# 2021-06-23_AD590_HIH-4031.net
KiCad netlist of a schematic drawn in EAGLE
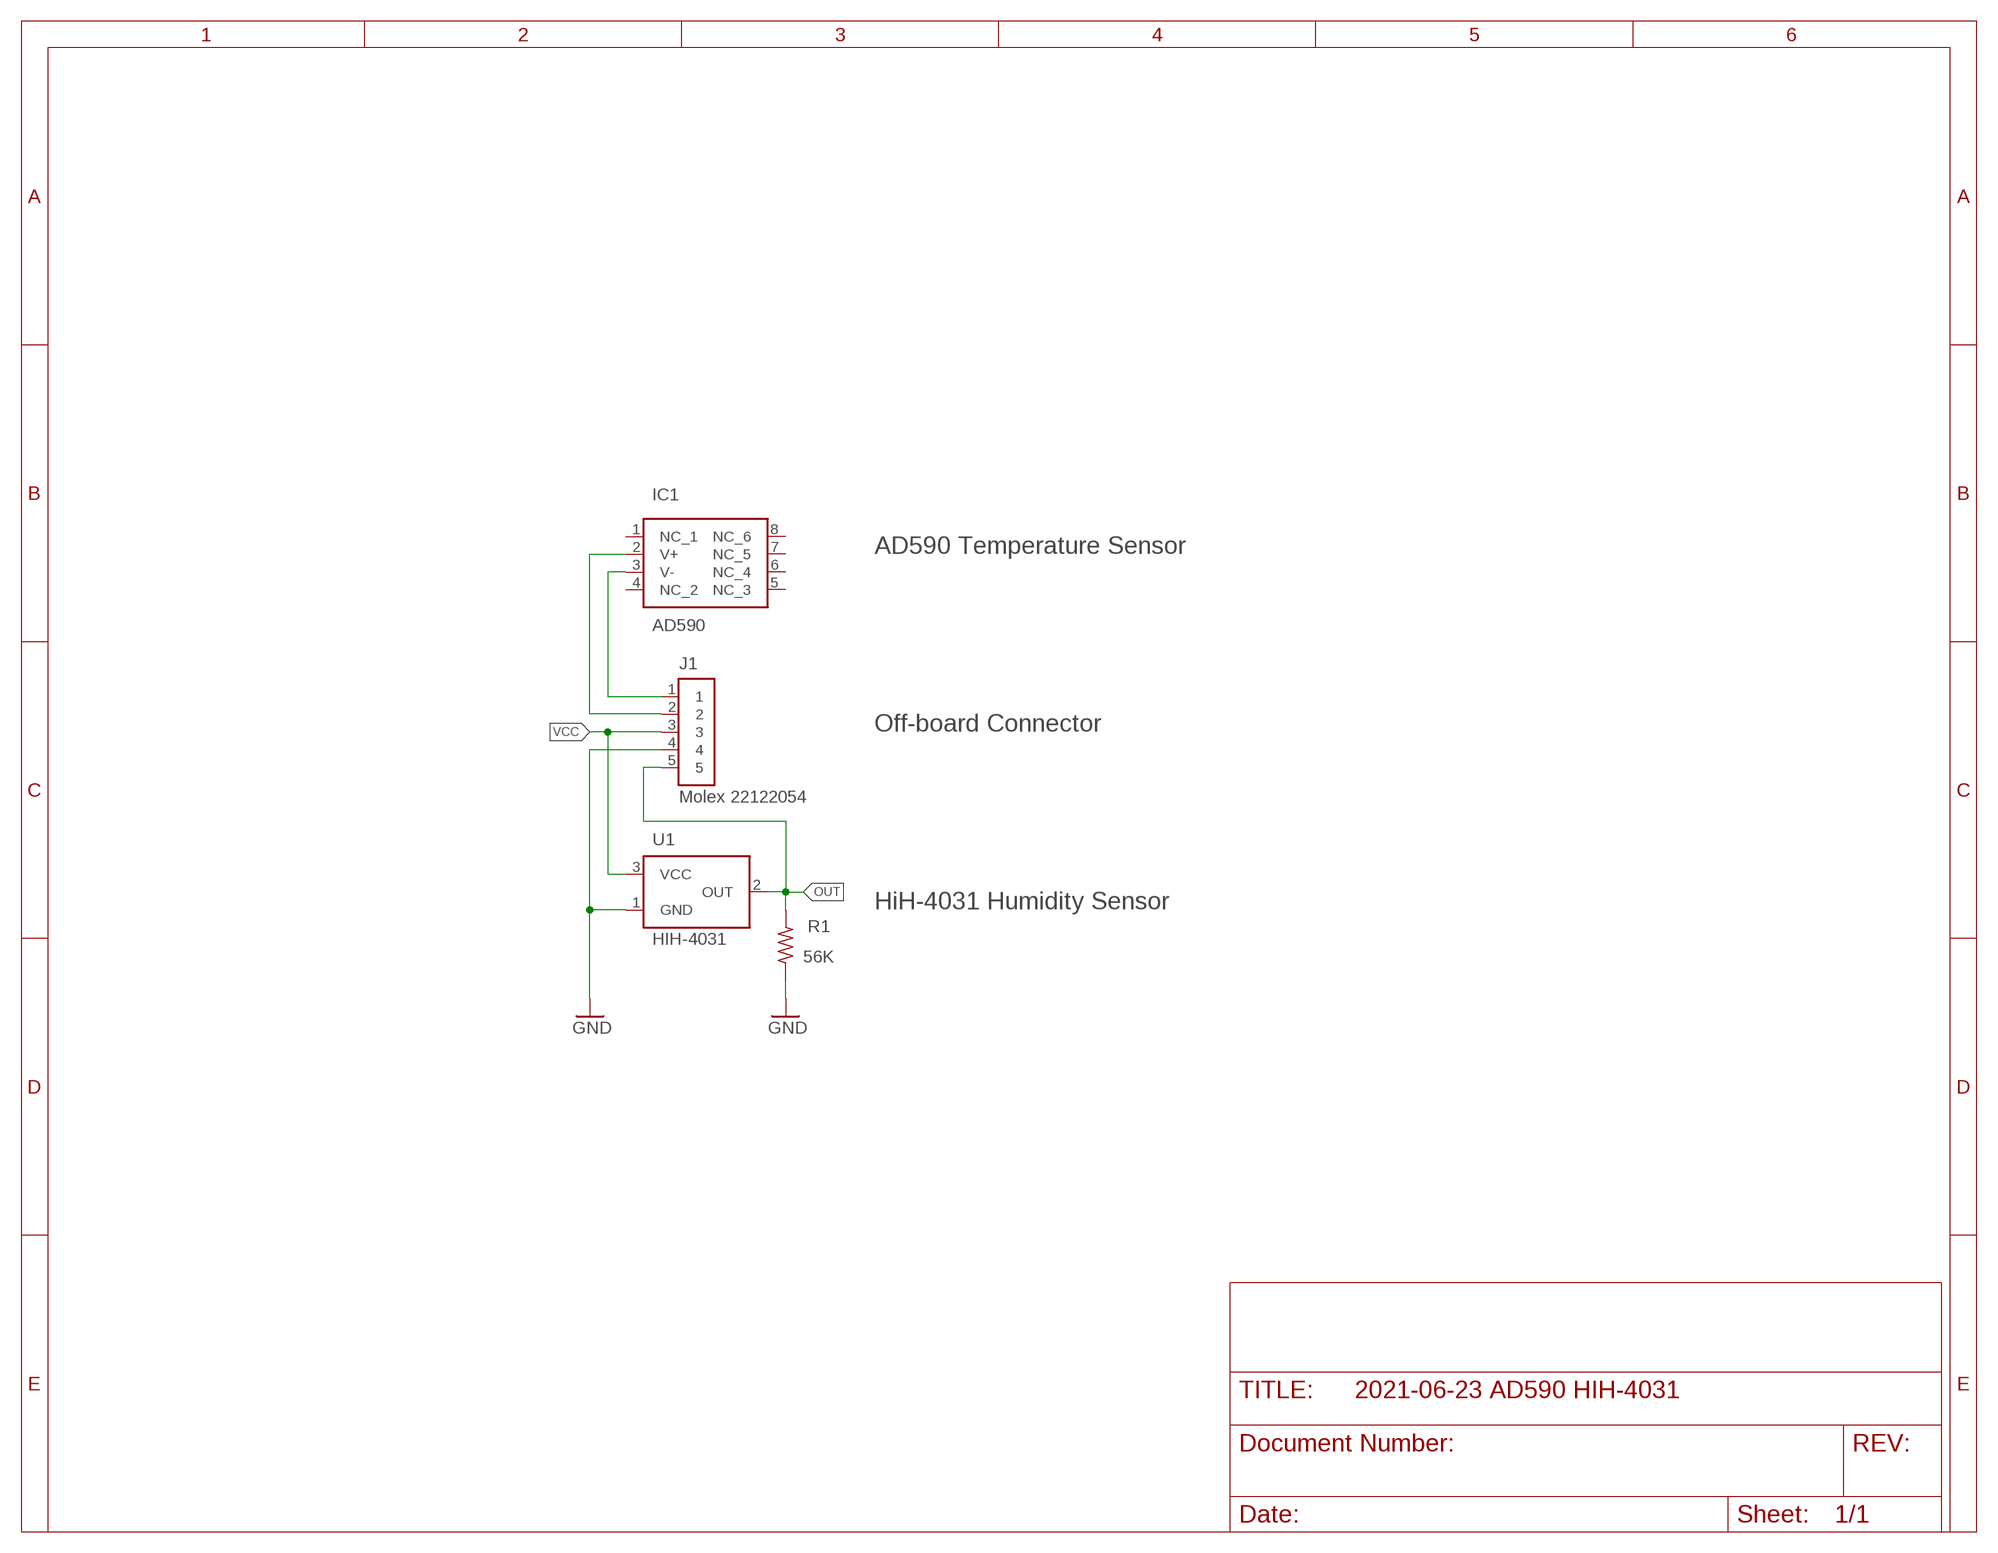
[diagram p0: schematic, sheet 1]

(export (version "E")
  (design (tool "Eeschema 10.0.6"))
  (components
    (comp (ref "IC1")
      (value "AD590")
      (footprint "eagle-import:SOIC127P600X175-8N")
      (fields
        (field (name "MANUFACTURER_PART_NUMBER") "AD590JRZ")
        (field (name "MOUSER_PART_NUMBER") "584-AD590JRZ")
        (field (name "RS_PART_NUMBER") "7096005P")
      )
      (libsource (lib "eagle-import") (part "AD590JRZ"))
    )
    (comp (ref "J1")
      (value "Molex 22122054")
      (footprint "eagle-import:1X05RA-MOLEX-22122054")
      (libsource (lib "eagle-import") (part "PINHD-1X5RA-MOLEX-22122054"))
    )
    (comp (ref "R1")
      (value "56K")
      (footprint "eagle-import:R0805")
      (libsource (lib "eagle-import") (part "R-US_R0805"))
    )
    (comp (ref "U1")
      (value "HIH-4031")
      (footprint "eagle-import:HIH-4030")
      (libsource (lib "eagle-import") (part "HIH-4030"))
    )
  )
  (nets
    (net (code "1") (name "GND") (class "Default")
      (node (ref "J1") (pin "4") (pinfunction "4_4") (pintype "bidirectional"))
      (node (ref "R1") (pin "1") (pinfunction "1_1") (pintype "passive"))
      (node (ref "U1") (pin "1") (pinfunction "GND_1") (pintype "bidirectional"))
    )
    (net (code "2") (name "Net-(IC1-V+)") (class "Default")
      (node (ref "IC1") (pin "2") (pinfunction "V+_2") (pintype "bidirectional"))
      (node (ref "J1") (pin "2") (pinfunction "2_2") (pintype "bidirectional"))
    )
    (net (code "3") (name "Net-(IC1-V-)") (class "Default")
      (node (ref "IC1") (pin "3") (pinfunction "V-_3") (pintype "bidirectional"))
      (node (ref "J1") (pin "1") (pinfunction "1_1") (pintype "bidirectional"))
    )
    (net (code "4") (name "OUT") (class "Default")
      (node (ref "J1") (pin "5") (pinfunction "5_5") (pintype "bidirectional"))
      (node (ref "R1") (pin "2") (pinfunction "2_2") (pintype "passive"))
      (node (ref "U1") (pin "2") (pinfunction "OUT_2") (pintype "bidirectional"))
    )
    (net (code "5") (name "VCC") (class "Default")
      (node (ref "J1") (pin "3") (pinfunction "3_3") (pintype "bidirectional"))
      (node (ref "U1") (pin "3") (pinfunction "VCC_3") (pintype "bidirectional"))
    )
    (net (code "6") (name "unconnected-(IC1-NC_1-Pad1)") (class "Default")
      (node (ref "IC1") (pin "1") (pinfunction "NC_1_1") (pintype "bidirectional"))
    )
    (net (code "7") (name "unconnected-(IC1-NC_2-Pad4)") (class "Default")
      (node (ref "IC1") (pin "4") (pinfunction "NC_2_4") (pintype "bidirectional"))
    )
    (net (code "8") (name "unconnected-(IC1-NC_3-Pad5)") (class "Default")
      (node (ref "IC1") (pin "5") (pinfunction "NC_3_5") (pintype "bidirectional"))
    )
    (net (code "9") (name "unconnected-(IC1-NC_4-Pad6)") (class "Default")
      (node (ref "IC1") (pin "6") (pinfunction "NC_4_6") (pintype "bidirectional"))
    )
    (net (code "10") (name "unconnected-(IC1-NC_5-Pad7)") (class "Default")
      (node (ref "IC1") (pin "7") (pinfunction "NC_5_7") (pintype "bidirectional"))
    )
    (net (code "11") (name "unconnected-(IC1-NC_6-Pad8)") (class "Default")
      (node (ref "IC1") (pin "8") (pinfunction "NC_6_8") (pintype "bidirectional"))
    )
  )
)
